# fpga_io_bank_1_PCIe.net
KiCad netlist of a schematic drawn in Altium Designer
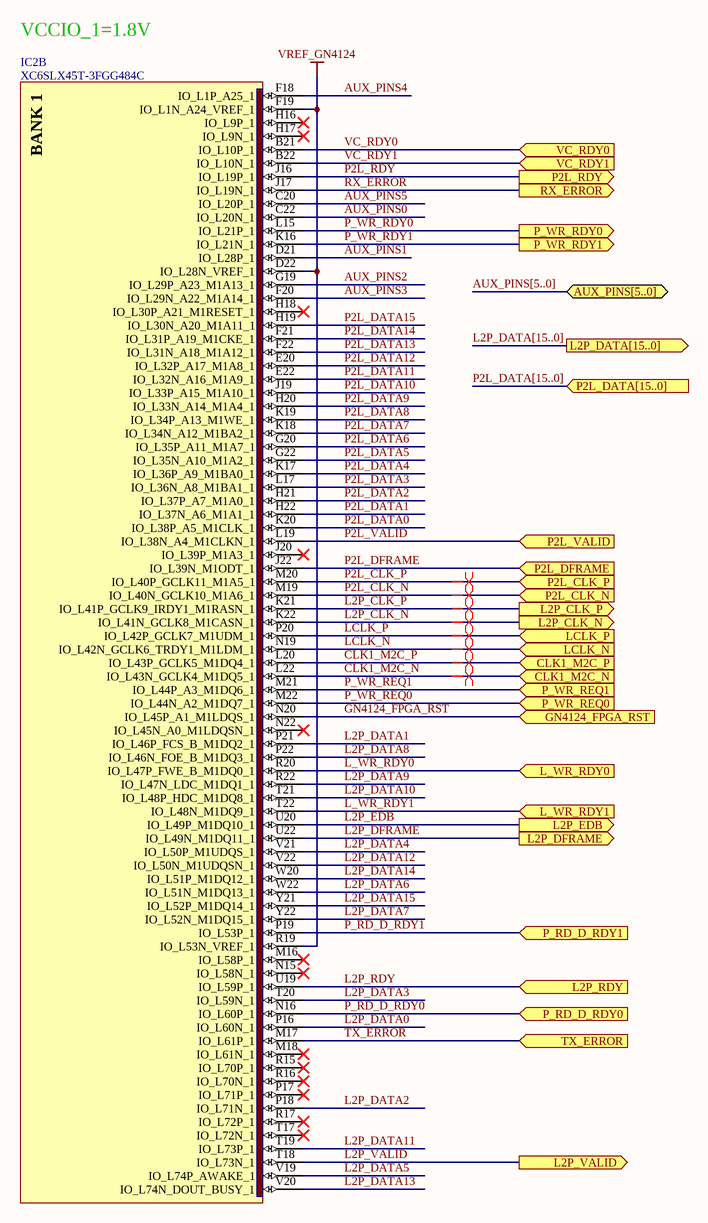
[diagram p0: fpga_io_bank_1_PCIe.SchDoc]

(export (version "E")
  (design (tool "Eeschema 10.0.6"))
  (components
    (comp (ref "IC2")
      (value "XC6SLX45T-3FGG484C")
      (footprint "BGA484C100P22X22_2300X2300X260")
      (fields (field (name "MANUFACTURER") "XILINX") (field (name "AUTHOR") "CERN DEM JLC"))
      (libsource (lib "ICs And Semiconductors") (part "XC6SLX45T-3FGG484C"))
    )
  )
  (nets
    (net (code "1") (name "/AUX_PINS0") (class "Default")
      (node (ref "IC2") (pin "C22") (pinfunction "IO_L20N_1_C22") (pintype "bidirectional"))
    )
    (net (code "2") (name "/AUX_PINS1") (class "Default")
      (node (ref "IC2") (pin "D21") (pinfunction "IO_L28P_1_D21") (pintype "bidirectional"))
    )
    (net (code "3") (name "/AUX_PINS2") (class "Default")
      (node (ref "IC2") (pin "G19") (pinfunction "IO_L29P_A23_M1A13_1_G19") (pintype "bidirectional"))
    )
    (net (code "4") (name "/AUX_PINS3") (class "Default")
      (node (ref "IC2") (pin "F20") (pinfunction "IO_L29N_A22_M1A14_1_F20") (pintype "bidirectional"))
    )
    (net (code "5") (name "/AUX_PINS4") (class "Default")
      (node (ref "IC2") (pin "F18") (pinfunction "IO_L1P_A25_1_F18") (pintype "bidirectional"))
    )
    (net (code "6") (name "/AUX_PINS5") (class "Default")
      (node (ref "IC2") (pin "C20") (pinfunction "IO_L20P_1_C20") (pintype "bidirectional"))
    )
    (net (code "8") (name "/CLK1_M2C_N") (class "Default")
      (node (ref "IC2") (pin "L22") (pinfunction "IO_L43N_GCLK4_M1DQ5_1_L22") (pintype "bidirectional"))
    )
    (net (code "9") (name "/CLK1_M2C_P") (class "Default")
      (node (ref "IC2") (pin "L20") (pinfunction "IO_L43P_GCLK5_M1DQ4_1_L20") (pintype "bidirectional"))
    )
    (net (code "10") (name "/GN4124_FPGA_RST") (class "Default")
      (node (ref "IC2") (pin "N20") (pinfunction "IO_L45P_A1_M1LDQS_1_N20") (pintype "bidirectional"))
    )
    (net (code "11") (name "/L2P_CLK_N") (class "Default")
      (node (ref "IC2") (pin "K22") (pinfunction "IO_L41N_GCLK8_M1CASN_1_K22") (pintype "bidirectional"))
    )
    (net (code "12") (name "/L2P_CLK_P") (class "Default")
      (node (ref "IC2") (pin "K21") (pinfunction "IO_L41P_GCLK9_IRDY1_M1RASN_1_K21") (pintype "bidirectional"))
    )
    (net (code "13") (name "/L2P_DATA0") (class "Default")
      (node (ref "IC2") (pin "P16") (pinfunction "IO_L60N_1_P16") (pintype "bidirectional"))
    )
    (net (code "14") (name "/L2P_DATA1") (class "Default")
      (node (ref "IC2") (pin "P21") (pinfunction "IO_L46P_FCS_B_M1DQ2_1_P21") (pintype "bidirectional"))
    )
    (net (code "15") (name "/L2P_DATA2") (class "Default")
      (node (ref "IC2") (pin "P18") (pinfunction "IO_L71N_1_P18") (pintype "bidirectional"))
    )
    (net (code "16") (name "/L2P_DATA3") (class "Default")
      (node (ref "IC2") (pin "T20") (pinfunction "IO_L59N_1_T20") (pintype "bidirectional"))
    )
    (net (code "17") (name "/L2P_DATA4") (class "Default")
      (node (ref "IC2") (pin "V21") (pinfunction "IO_L50P_M1UDQS_1_V21") (pintype "bidirectional"))
    )
    (net (code "18") (name "/L2P_DATA5") (class "Default")
      (node (ref "IC2") (pin "V19") (pinfunction "IO_L74P_AWAKE_1_V19") (pintype "bidirectional"))
    )
    (net (code "19") (name "/L2P_DATA6") (class "Default")
      (node (ref "IC2") (pin "W22") (pinfunction "IO_L51N_M1DQ13_1_W22") (pintype "bidirectional"))
    )
    (net (code "20") (name "/L2P_DATA7") (class "Default")
      (node (ref "IC2") (pin "Y22") (pinfunction "IO_L52N_M1DQ15_1_Y22") (pintype "bidirectional"))
    )
    (net (code "21") (name "/L2P_DATA8") (class "Default")
      (node (ref "IC2") (pin "P22") (pinfunction "IO_L46N_FOE_B_M1DQ3_1_P22") (pintype "bidirectional"))
    )
    (net (code "22") (name "/L2P_DATA9") (class "Default")
      (node (ref "IC2") (pin "R22") (pinfunction "IO_L47N_LDC_M1DQ1_1_R22") (pintype "bidirectional"))
    )
    (net (code "23") (name "/L2P_DATA10") (class "Default")
      (node (ref "IC2") (pin "T21") (pinfunction "IO_L48P_HDC_M1DQ8_1_T21") (pintype "bidirectional"))
    )
    (net (code "24") (name "/L2P_DATA11") (class "Default")
      (node (ref "IC2") (pin "T19") (pinfunction "IO_L73P_1_T19") (pintype "bidirectional"))
    )
    (net (code "25") (name "/L2P_DATA12") (class "Default")
      (node (ref "IC2") (pin "V22") (pinfunction "IO_L50N_M1UDQSN_1_V22") (pintype "bidirectional"))
    )
    (net (code "26") (name "/L2P_DATA13") (class "Default")
      (node (ref "IC2") (pin "V20") (pinfunction "IO_L74N_DOUT_BUSY_1_V20") (pintype "bidirectional"))
    )
    (net (code "27") (name "/L2P_DATA14") (class "Default")
      (node (ref "IC2") (pin "W20") (pinfunction "IO_L51P_M1DQ12_1_W20") (pintype "bidirectional"))
    )
    (net (code "28") (name "/L2P_DATA15") (class "Default")
      (node (ref "IC2") (pin "Y21") (pinfunction "IO_L52P_M1DQ14_1_Y21") (pintype "bidirectional"))
    )
    (net (code "30") (name "/L2P_DFRAME") (class "Default")
      (node (ref "IC2") (pin "U22") (pinfunction "IO_L49N_M1DQ11_1_U22") (pintype "bidirectional"))
    )
    (net (code "31") (name "/L2P_EDB") (class "Default")
      (node (ref "IC2") (pin "U20") (pinfunction "IO_L49P_M1DQ10_1_U20") (pintype "bidirectional"))
    )
    (net (code "32") (name "/L2P_RDY") (class "Default")
      (node (ref "IC2") (pin "U19") (pinfunction "IO_L59P_1_U19") (pintype "bidirectional"))
    )
    (net (code "33") (name "/L2P_VALID") (class "Default")
      (node (ref "IC2") (pin "T18") (pinfunction "IO_L73N_1_T18") (pintype "bidirectional"))
    )
    (net (code "34") (name "/LCLK_N") (class "Default")
      (node (ref "IC2") (pin "N19") (pinfunction "IO_L42N_GCLK6_TRDY1_M1LDM_1_N19") (pintype "bidirectional"))
    )
    (net (code "35") (name "/LCLK_P") (class "Default")
      (node (ref "IC2") (pin "P20") (pinfunction "IO_L42P_GCLK7_M1UDM_1_P20") (pintype "bidirectional"))
    )
    (net (code "36") (name "/L_WR_RDY0") (class "Default")
      (node (ref "IC2") (pin "R20") (pinfunction "IO_L47P_FWE_B_M1DQ0_1_R20") (pintype "bidirectional"))
    )
    (net (code "37") (name "/L_WR_RDY1") (class "Default")
      (node (ref "IC2") (pin "T22") (pinfunction "IO_L48N_M1DQ9_1_T22") (pintype "bidirectional"))
    )
    (net (code "38") (name "/P2L_CLK_N") (class "Default")
      (node (ref "IC2") (pin "M19") (pinfunction "IO_L40N_GCLK10_M1A6_1_M19") (pintype "bidirectional"))
    )
    (net (code "39") (name "/P2L_CLK_P") (class "Default")
      (node (ref "IC2") (pin "M20") (pinfunction "IO_L40P_GCLK11_M1A5_1_M20") (pintype "bidirectional"))
    )
    (net (code "40") (name "/P2L_DATA0") (class "Default")
      (node (ref "IC2") (pin "K20") (pinfunction "IO_L38P_A5_M1CLK_1_K20") (pintype "bidirectional"))
    )
    (net (code "41") (name "/P2L_DATA1") (class "Default")
      (node (ref "IC2") (pin "H22") (pinfunction "IO_L37N_A6_M1A1_1_H22") (pintype "bidirectional"))
    )
    (net (code "42") (name "/P2L_DATA2") (class "Default")
      (node (ref "IC2") (pin "H21") (pinfunction "IO_L37P_A7_M1A0_1_H21") (pintype "bidirectional"))
    )
    (net (code "43") (name "/P2L_DATA3") (class "Default")
      (node (ref "IC2") (pin "L17") (pinfunction "IO_L36N_A8_M1BA1_1_L17") (pintype "bidirectional"))
    )
    (net (code "44") (name "/P2L_DATA4") (class "Default")
      (node (ref "IC2") (pin "K17") (pinfunction "IO_L36P_A9_M1BA0_1_K17") (pintype "bidirectional"))
    )
    (net (code "45") (name "/P2L_DATA5") (class "Default")
      (node (ref "IC2") (pin "G22") (pinfunction "IO_L35N_A10_M1A2_1_G22") (pintype "bidirectional"))
    )
    (net (code "46") (name "/P2L_DATA6") (class "Default")
      (node (ref "IC2") (pin "G20") (pinfunction "IO_L35P_A11_M1A7_1_G20") (pintype "bidirectional"))
    )
    (net (code "47") (name "/P2L_DATA7") (class "Default")
      (node (ref "IC2") (pin "K18") (pinfunction "IO_L34N_A12_M1BA2_1_K18") (pintype "bidirectional"))
    )
    (net (code "48") (name "/P2L_DATA8") (class "Default")
      (node (ref "IC2") (pin "K19") (pinfunction "IO_L34P_A13_M1WE_1_K19") (pintype "bidirectional"))
    )
    (net (code "49") (name "/P2L_DATA9") (class "Default")
      (node (ref "IC2") (pin "H20") (pinfunction "IO_L33N_A14_M1A4_1_H20") (pintype "bidirectional"))
    )
    (net (code "50") (name "/P2L_DATA10") (class "Default")
      (node (ref "IC2") (pin "J19") (pinfunction "IO_L33P_A15_M1A10_1_J19") (pintype "bidirectional"))
    )
    (net (code "51") (name "/P2L_DATA11") (class "Default")
      (node (ref "IC2") (pin "E22") (pinfunction "IO_L32N_A16_M1A9_1_E22") (pintype "bidirectional"))
    )
    (net (code "52") (name "/P2L_DATA12") (class "Default")
      (node (ref "IC2") (pin "E20") (pinfunction "IO_L32P_A17_M1A8_1_E20") (pintype "bidirectional"))
    )
    (net (code "53") (name "/P2L_DATA13") (class "Default")
      (node (ref "IC2") (pin "F22") (pinfunction "IO_L31N_A18_M1A12_1_F22") (pintype "bidirectional"))
    )
    (net (code "54") (name "/P2L_DATA14") (class "Default")
      (node (ref "IC2") (pin "F21") (pinfunction "IO_L31P_A19_M1CKE_1_F21") (pintype "bidirectional"))
    )
    (net (code "55") (name "/P2L_DATA15") (class "Default")
      (node (ref "IC2") (pin "H19") (pinfunction "IO_L30N_A20_M1A11_1_H19") (pintype "bidirectional"))
    )
    (net (code "57") (name "/P2L_DFRAME") (class "Default")
      (node (ref "IC2") (pin "J22") (pinfunction "IO_L39N_M1ODT_1_J22") (pintype "bidirectional"))
    )
    (net (code "58") (name "/P2L_RDY") (class "Default")
      (node (ref "IC2") (pin "J16") (pinfunction "IO_L19P_1_J16") (pintype "bidirectional"))
    )
    (net (code "59") (name "/P2L_VALID") (class "Default")
      (node (ref "IC2") (pin "L19") (pinfunction "IO_L38N_A4_M1CLKN_1_L19") (pintype "bidirectional"))
    )
    (net (code "60") (name "/P_RD_D_RDY0") (class "Default")
      (node (ref "IC2") (pin "N16") (pinfunction "IO_L60P_1_N16") (pintype "bidirectional"))
    )
    (net (code "61") (name "/P_RD_D_RDY1") (class "Default")
      (node (ref "IC2") (pin "P19") (pinfunction "IO_L53P_1_P19") (pintype "bidirectional"))
    )
    (net (code "62") (name "/P_WR_RDY0") (class "Default")
      (node (ref "IC2") (pin "L15") (pinfunction "IO_L21P_1_L15") (pintype "bidirectional"))
    )
    (net (code "63") (name "/P_WR_RDY1") (class "Default")
      (node (ref "IC2") (pin "K16") (pinfunction "IO_L21N_1_K16") (pintype "bidirectional"))
    )
    (net (code "64") (name "/P_WR_REQ0") (class "Default")
      (node (ref "IC2") (pin "M22") (pinfunction "IO_L44N_A2_M1DQ7_1_M22") (pintype "bidirectional"))
    )
    (net (code "65") (name "/P_WR_REQ1") (class "Default")
      (node (ref "IC2") (pin "M21") (pinfunction "IO_L44P_A3_M1DQ6_1_M21") (pintype "bidirectional"))
    )
    (net (code "66") (name "/RX_ERROR") (class "Default")
      (node (ref "IC2") (pin "J17") (pinfunction "IO_L19N_1_J17") (pintype "bidirectional"))
    )
    (net (code "67") (name "/TX_ERROR") (class "Default")
      (node (ref "IC2") (pin "M17") (pinfunction "IO_L61P_1_M17") (pintype "bidirectional"))
    )
    (net (code "68") (name "/VC_RDY0") (class "Default")
      (node (ref "IC2") (pin "B21") (pinfunction "IO_L10P_1_B21") (pintype "bidirectional"))
    )
    (net (code "69") (name "/VC_RDY1") (class "Default")
      (node (ref "IC2") (pin "B22") (pinfunction "IO_L10N_1_B22") (pintype "bidirectional"))
    )
    (net (code "70") (name "VREF_GN4124") (class "Default")
      (node (ref "IC2") (pin "D22") (pinfunction "IO_L28N_VREF_1_D22") (pintype "bidirectional"))
      (node (ref "IC2") (pin "F19") (pinfunction "IO_L1N_A24_VREF_1_F19") (pintype "bidirectional"))
      (node (ref "IC2") (pin "R19") (pinfunction "IO_L53N_VREF_1_R19") (pintype "bidirectional"))
    )
    (net (code "71") (name "unconnected-(IC2B-IO_L9N_1-PadH17)") (class "Default")
      (node (ref "IC2") (pin "H17") (pinfunction "IO_L9N_1_H17") (pintype "bidirectional+no_connect"))
    )
    (net (code "72") (name "unconnected-(IC2B-IO_L9P_1-PadH16)") (class "Default")
      (node (ref "IC2") (pin "H16") (pinfunction "IO_L9P_1_H16") (pintype "bidirectional+no_connect"))
    )
    (net (code "73") (name "unconnected-(IC2B-IO_L30P_A21_M1RESET_1-PadH18)") (class "Default")
      (node (ref "IC2") (pin "H18") (pinfunction "IO_L30P_A21_M1RESET_1_H18") (pintype "bidirectional+no_connect"))
    )
    (net (code "74") (name "unconnected-(IC2B-IO_L39P_M1A3_1-PadJ20)") (class "Default")
      (node (ref "IC2") (pin "J20") (pinfunction "IO_L39P_M1A3_1_J20") (pintype "bidirectional+no_connect"))
    )
    (net (code "75") (name "unconnected-(IC2B-IO_L45N_A0_M1LDQSN_1-PadN22)") (class "Default")
      (node (ref "IC2") (pin "N22") (pinfunction "IO_L45N_A0_M1LDQSN_1_N22") (pintype "bidirectional+no_connect"))
    )
    (net (code "76") (name "unconnected-(IC2B-IO_L58N_1-PadN15)") (class "Default")
      (node (ref "IC2") (pin "N15") (pinfunction "IO_L58N_1_N15") (pintype "bidirectional+no_connect"))
    )
    (net (code "77") (name "unconnected-(IC2B-IO_L58P_1-PadM16)") (class "Default")
      (node (ref "IC2") (pin "M16") (pinfunction "IO_L58P_1_M16") (pintype "bidirectional+no_connect"))
    )
    (net (code "78") (name "unconnected-(IC2B-IO_L61N_1-PadM18)") (class "Default")
      (node (ref "IC2") (pin "M18") (pinfunction "IO_L61N_1_M18") (pintype "bidirectional+no_connect"))
    )
    (net (code "79") (name "unconnected-(IC2B-IO_L70N_1-PadR16)") (class "Default")
      (node (ref "IC2") (pin "R16") (pinfunction "IO_L70N_1_R16") (pintype "bidirectional+no_connect"))
    )
    (net (code "80") (name "unconnected-(IC2B-IO_L70P_1-PadR15)") (class "Default")
      (node (ref "IC2") (pin "R15") (pinfunction "IO_L70P_1_R15") (pintype "bidirectional+no_connect"))
    )
    (net (code "81") (name "unconnected-(IC2B-IO_L71P_1-PadP17)") (class "Default")
      (node (ref "IC2") (pin "P17") (pinfunction "IO_L71P_1_P17") (pintype "bidirectional+no_connect"))
    )
    (net (code "82") (name "unconnected-(IC2B-IO_L72N_1-PadT17)") (class "Default")
      (node (ref "IC2") (pin "T17") (pinfunction "IO_L72N_1_T17") (pintype "bidirectional+no_connect"))
    )
    (net (code "83") (name "unconnected-(IC2B-IO_L72P_1-PadR17)") (class "Default")
      (node (ref "IC2") (pin "R17") (pinfunction "IO_L72P_1_R17") (pintype "bidirectional+no_connect"))
    )
  )
)
